# Analog_Input_Connector.net
KiCad netlist of a schematic drawn in Altium Designer
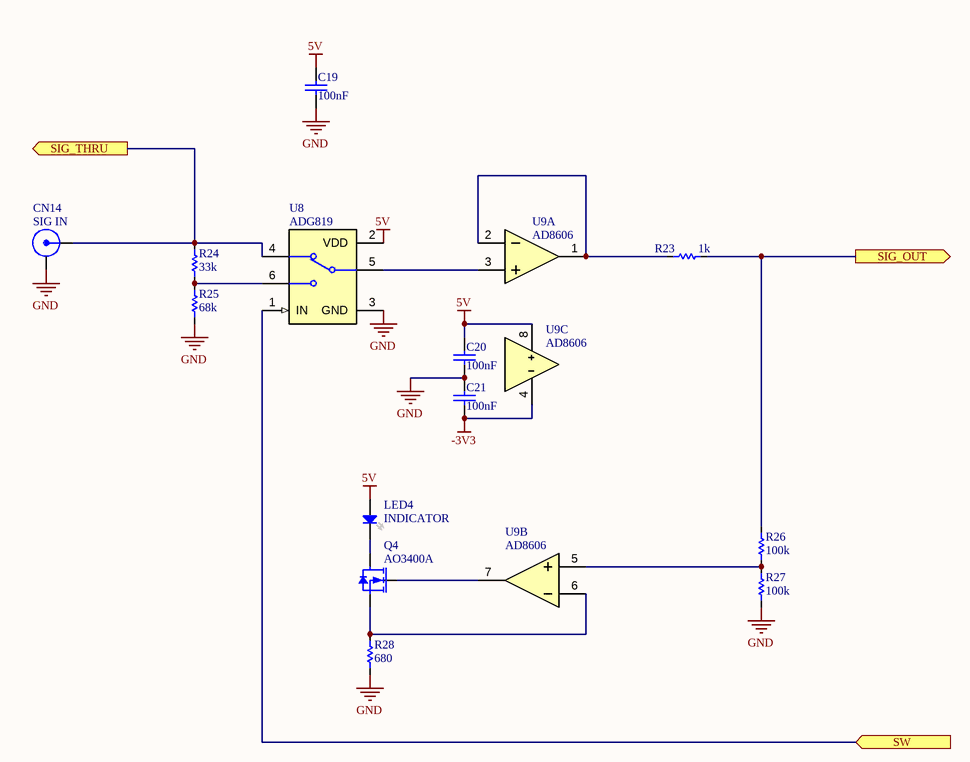
[diagram p0: Analog Input Connector.SchDoc]

(export (version "E")
  (design (tool "Eeschema 10.0.6"))
  (components
    (comp (ref "C19")
      (value "100nF")
      (footprint "CAP_CHIP_0603")
      (description "0603 Multilayer Ceramic Capacitors MLCC")
      (fields (field (name "TOLERANCE") "10%") (field (name "PARTNUMBER") "CC0603KRX7R9BB104"))
      (libsource (lib "Sainsbury Wellcome Centre") (part "Cap"))
    )
    (comp (ref "C20")
      (value "100nF")
      (footprint "CAP_CHIP_0603")
      (description "0603 Multilayer Ceramic Capacitors MLCC")
      (fields (field (name "TOLERANCE") "10%") (field (name "PARTNUMBER") "CC0603KRX7R9BB104"))
      (libsource (lib "Sainsbury Wellcome Centre") (part "Cap"))
    )
    (comp (ref "C21")
      (value "100nF")
      (footprint "CAP_CHIP_0603")
      (description "0603 Multilayer Ceramic Capacitors MLCC")
      (fields (field (name "TOLERANCE") "10%") (field (name "PARTNUMBER") "CC0603KRX7R9BB104"))
      (libsource (lib "Sainsbury Wellcome Centre") (part "Cap"))
    )
    (comp (ref "CN14")
      (value "SIG IN")
      (footprint "BNC-AMP-112515")
      (description "RF BNC Connector, Female, Board Mount, Solder Terminal, Jack")
      (fields (field (name "PARTNUMBER") "112515"))
      (libsource (lib "Sainsbury Wellcome Centre") (part "RF-Jack"))
    )
    (comp (ref "LED4")
      (value "INDICATOR")
      (footprint "LED_CHIP_0805")
      (description "White 0805 Light Emitting Diodes (LED) ROHS")
      (fields (field (name "PARTNUMBER") "KT-0805W"))
      (libsource (lib "Sainsbury Wellcome Centre") (part "LED-WHITE"))
    )
    (comp (ref "Q4")
      (value "AO3400A")
      (footprint "SOT23")
      (description "30V 5.7A 26.5mΩ@10V,5.7A 1.4W 1.5V@250uA 1 NChannel SOT-23-3L MOSFETs")
      (fields (field (name "PARTNUMBER") "AO3400A"))
      (libsource (lib "Sainsbury Wellcome Centre") (part "NMOS"))
    )
    (comp (ref "R23")
      (value "1k")
      (footprint "RES_CHIP_0603")
      (description "100mW Thick Film Resistors 75V ±100ppm/℃ ±1% 0603 Chip Resistor")
      (fields (field (name "PARTNUMBER") "0603WAF1001T5E") (field (name "TOLERANCE") "1%"))
      (libsource (lib "Sainsbury Wellcome Centre") (part "Res"))
    )
    (comp (ref "R24")
      (value "33k")
      (footprint "RES_CHIP_0603")
      (description "100mW Thick Film Resistors 75V ±100ppm/℃ ±1% 0603 Chip Resistor")
      (fields (field (name "TOLERANCE") "1%") (field (name "PARTNUMBER") "0603WAF3302T5E"))
      (libsource (lib "Sainsbury Wellcome Centre") (part "Res"))
    )
    (comp (ref "R25")
      (value "68k")
      (footprint "RES_CHIP_0603")
      (description "100mW Thick Film Resistors 75V ±100ppm/℃ ±1% 0603 Chip Resistor")
      (fields (field (name "TOLERANCE") "1%") (field (name "PARTNUMBER") "0603WAF6802T5E"))
      (libsource (lib "Sainsbury Wellcome Centre") (part "Res"))
    )
    (comp (ref "R26")
      (value "100k")
      (footprint "RES_CHIP_0603")
      (description "100mW Thick Film Resistors 75V ±100ppm/℃ ±1% 0603 Chip Resistor")
      (fields (field (name "PARTNUMBER") "0603WAF1003T5E") (field (name "TOLERANCE") "1%"))
      (libsource (lib "Sainsbury Wellcome Centre") (part "Res"))
    )
    (comp (ref "R27")
      (value "100k")
      (footprint "RES_CHIP_0603")
      (description "100mW Thick Film Resistors 75V ±100ppm/℃ ±1% 0603 Chip Resistor")
      (fields (field (name "PARTNUMBER") "0603WAF1003T5E") (field (name "TOLERANCE") "1%"))
      (libsource (lib "Sainsbury Wellcome Centre") (part "Res"))
    )
    (comp (ref "R28")
      (value "680")
      (footprint "RES_CHIP_0603")
      (description "100mW Thick Film Resistors 75V ±100ppm/℃ ±1% 0603 Chip Resistor")
      (fields (field (name "PARTNUMBER") "0603WAF6800T5E") (field (name "TOLERANCE") "1%"))
      (libsource (lib "Sainsbury Wellcome Centre") (part "Res"))
    )
    (comp (ref "U8")
      (value "ADG819")
      (footprint "SOT23-6")
      (description "Analog Switch/Analog Multiplexer Single 2: 1 Automotive 6-Pin SOT-23 T/R")
      (fields (field (name "PARTNUMBER") "ADG819BRTZ-REEL7"))
      (libsource (lib "Sainsbury Wellcome Centre") (part "ADG819"))
    )
    (comp (ref "U9")
      (value "AD8606")
      (footprint "VSSOP8_3X3_0.65E")
      (description "Operational Amplifier, 2 Func, 750uV Offset-Max, CMOS, PDSO8")
      (fields (field (name "PARTNUMBER") "AD8606ARMZ-REEL"))
      (libsource (lib "Sainsbury Wellcome Centre") (part "OPAMP 8P"))
    )
  )
  (nets
    (net (code "1") (name "-3V3") (class "Default")
      (node (ref "C21") (pin "1") (pinfunction "1_1") (pintype "passive"))
      (node (ref "U9") (pin "4") (pinfunction "V-_4") (pintype "power_in"))
    )
    (net (code "2") (name "/SIG_OUT") (class "Default")
      (node (ref "R23") (pin "2") (pinfunction "2_2") (pintype "passive"))
      (node (ref "R26") (pin "2") (pinfunction "2_2") (pintype "passive"))
    )
    (net (code "3") (name "/SIG_THRU") (class "Default")
      (node (ref "CN14") (pin "1") (pinfunction "SIG_1") (pintype "passive"))
      (node (ref "R24") (pin "2") (pinfunction "2_2") (pintype "passive"))
      (node (ref "U8") (pin "4") (pinfunction "S1_4") (pintype "passive"))
    )
    (net (code "4") (name "/SW") (class "Default")
      (node (ref "U8") (pin "1") (pinfunction "IN_1") (pintype "input"))
    )
    (net (code "5") (name "5V") (class "Default")
      (node (ref "C19") (pin "2") (pinfunction "2_2") (pintype "passive"))
      (node (ref "C20") (pin "2") (pinfunction "2_2") (pintype "passive"))
      (node (ref "LED4") (pin "2") (pinfunction "A_2") (pintype "passive"))
      (node (ref "U8") (pin "2") (pinfunction "VDD_2") (pintype "power_in"))
      (node (ref "U9") (pin "8") (pinfunction "V+_8") (pintype "power_in"))
    )
    (net (code "6") (name "GND") (class "Default")
      (node (ref "C19") (pin "1") (pinfunction "1_1") (pintype "passive"))
      (node (ref "C20") (pin "1") (pinfunction "1_1") (pintype "passive"))
      (node (ref "C21") (pin "2") (pinfunction "2_2") (pintype "passive"))
      (node (ref "CN14") (pin "2") (pinfunction "GND_2") (pintype "passive"))
      (node (ref "R25") (pin "1") (pinfunction "1_1") (pintype "passive"))
      (node (ref "R27") (pin "1") (pinfunction "1_1") (pintype "passive"))
      (node (ref "R28") (pin "1") (pinfunction "1_1") (pintype "passive"))
      (node (ref "U8") (pin "3") (pinfunction "GND_3") (pintype "power_in"))
    )
    (net (code "7") (name "Net-(LED4-K)") (class "Default")
      (node (ref "LED4") (pin "1") (pinfunction "K_1") (pintype "passive"))
      (node (ref "Q4") (pin "3") (pinfunction "D_3") (pintype "passive"))
    )
    (net (code "8") (name "Net-(Q4-G)") (class "Default")
      (node (ref "Q4") (pin "1") (pinfunction "G_1") (pintype "passive"))
      (node (ref "U9") (pin "7") (pinfunction "BOUT_7") (pintype "passive"))
    )
    (net (code "9") (name "Net-(Q4-S)") (class "Default")
      (node (ref "Q4") (pin "2") (pinfunction "S_2") (pintype "passive"))
      (node (ref "R28") (pin "2") (pinfunction "2_2") (pintype "passive"))
      (node (ref "U9") (pin "6") (pinfunction "B-_6") (pintype "passive"))
    )
    (net (code "10") (name "Net-(U8-D)") (class "Default")
      (node (ref "U8") (pin "5") (pinfunction "D_5") (pintype "passive"))
      (node (ref "U9") (pin "3") (pinfunction "A+_3") (pintype "passive"))
    )
    (net (code "11") (name "Net-(U8-S2)") (class "Default")
      (node (ref "R24") (pin "1") (pinfunction "1_1") (pintype "passive"))
      (node (ref "R25") (pin "2") (pinfunction "2_2") (pintype "passive"))
      (node (ref "U8") (pin "6") (pinfunction "S2_6") (pintype "passive"))
    )
    (net (code "12") (name "Net-(U9A-A-)") (class "Default")
      (node (ref "R23") (pin "1") (pinfunction "1_1") (pintype "passive"))
      (node (ref "U9") (pin "1") (pinfunction "AOUT_1") (pintype "passive"))
      (node (ref "U9") (pin "2") (pinfunction "A-_2") (pintype "passive"))
    )
    (net (code "13") (name "Net-(U9B-B+)") (class "Default")
      (node (ref "R26") (pin "1") (pinfunction "1_1") (pintype "passive"))
      (node (ref "R27") (pin "2") (pinfunction "2_2") (pintype "passive"))
      (node (ref "U9") (pin "5") (pinfunction "B+_5") (pintype "passive"))
    )
  )
)
